# Main.net
KiCad netlist of a schematic drawn in Altium Designer
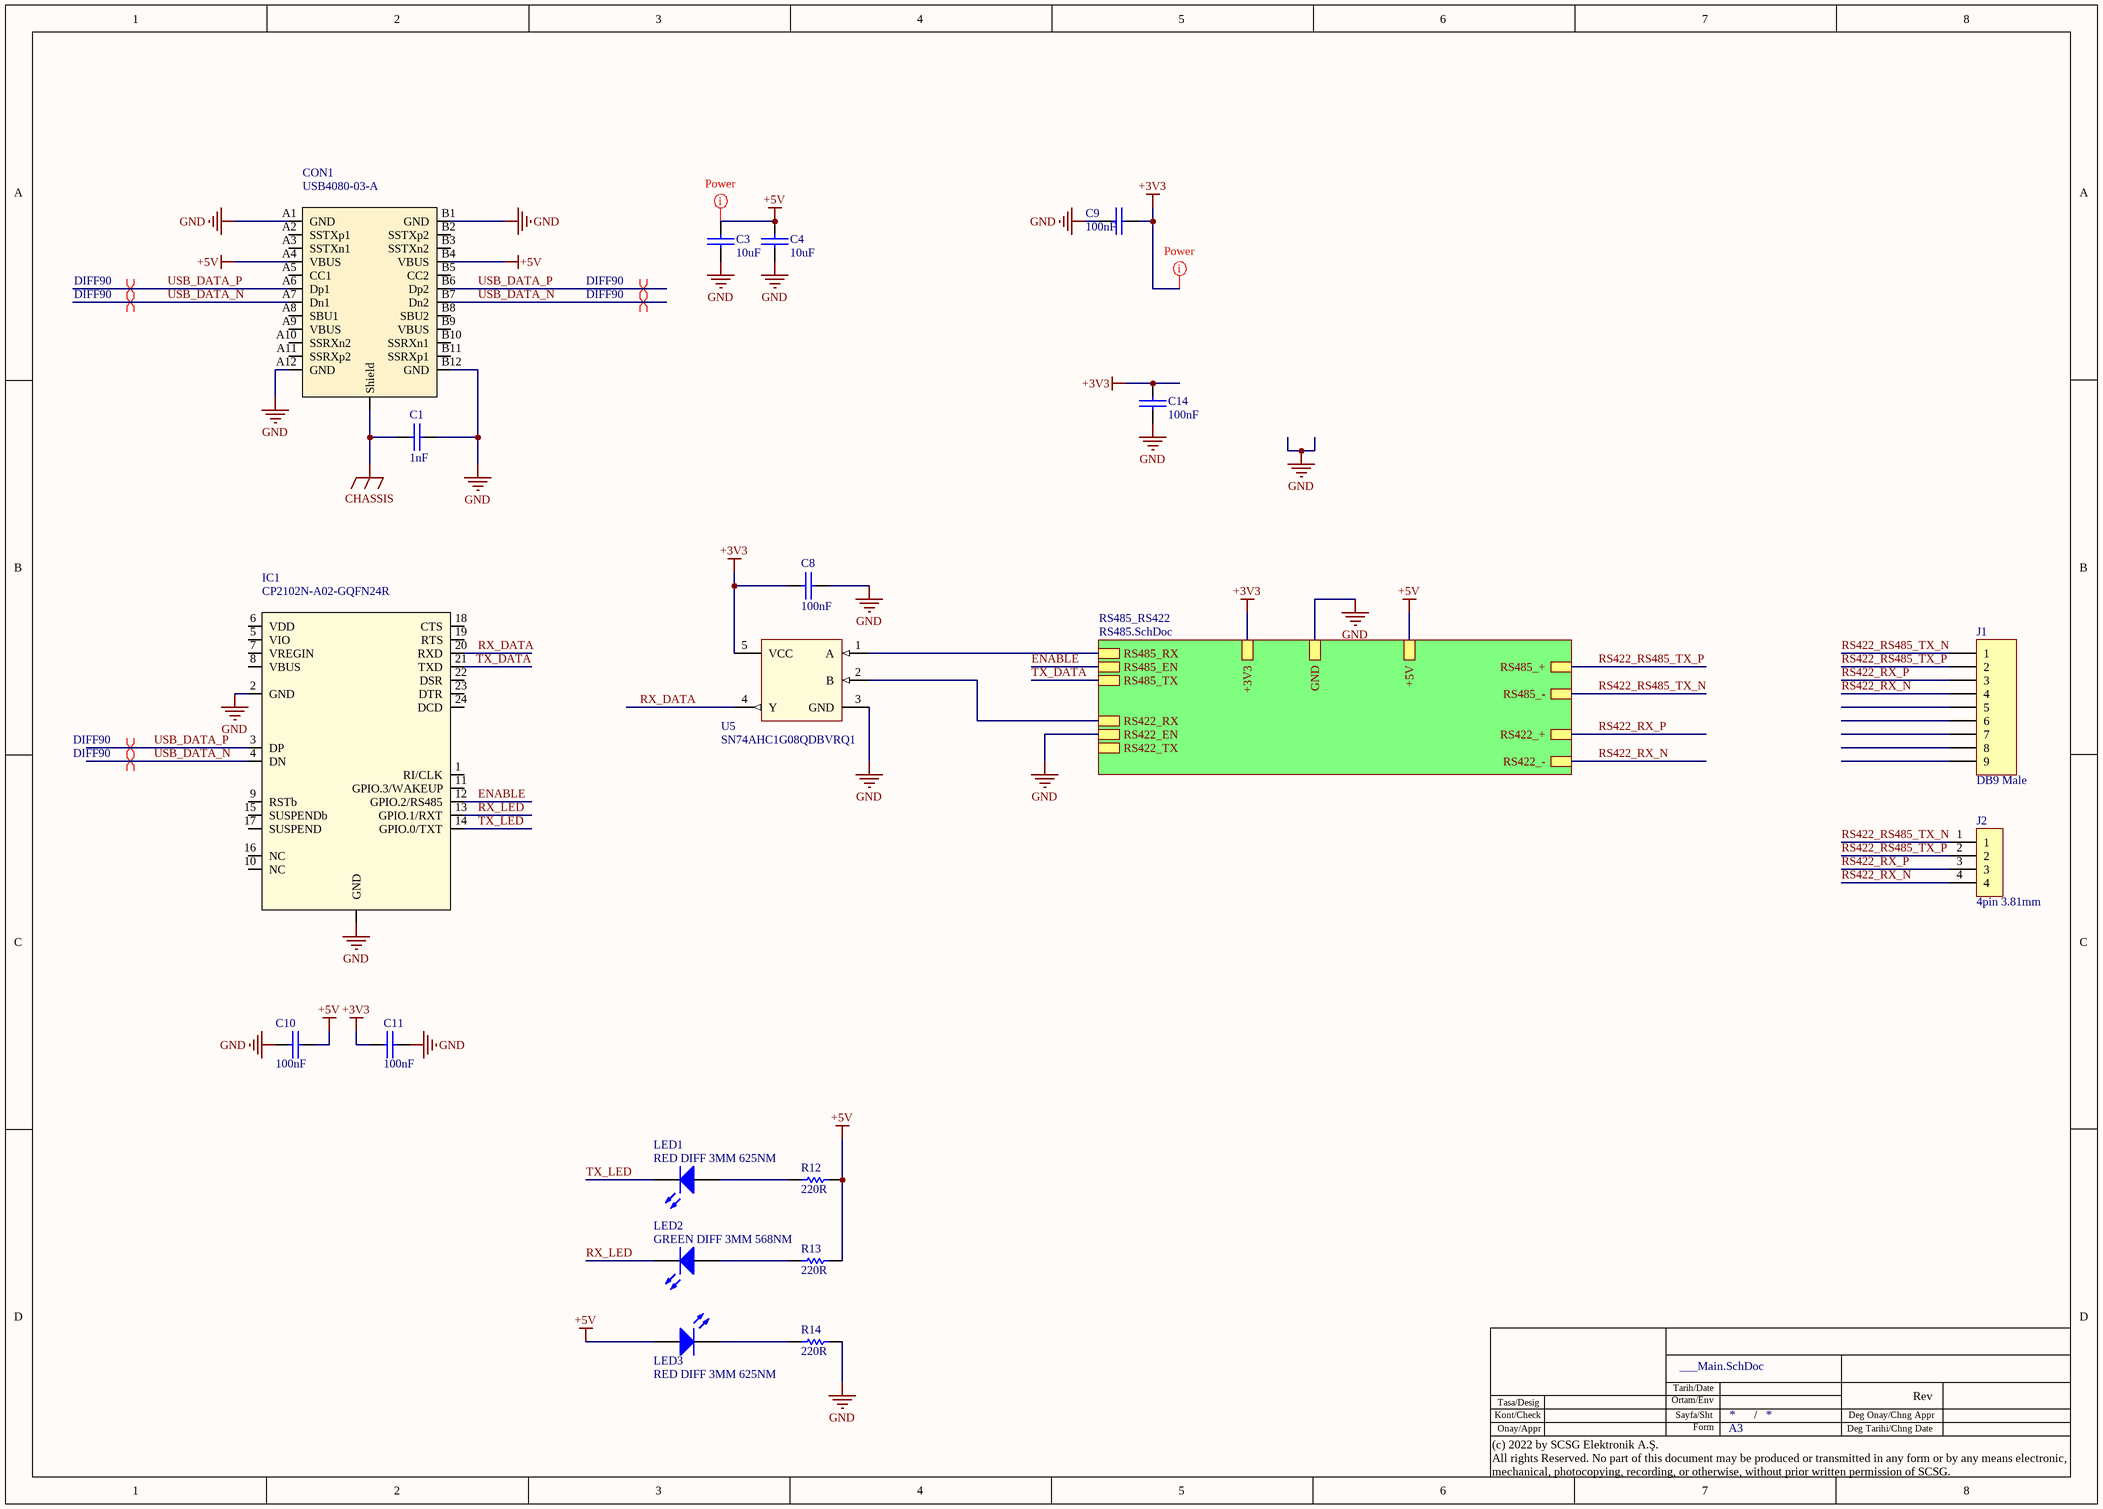
[diagram p0: ___Main.SchDoc]

(export (version "E")
  (design (tool "Eeschema 10.0.6"))
  (components
    (comp (ref "C1")
      (value "1nF")
      (footprint "C1206-N - H 1.75×L 3.4×W 1.8")
      (description "1nF, 1206, X7R, 2kV, % 10, AEC-Q200")
      (fields (field (name "MANUFACTURER") "Kemet") (field (name "TOLERANCE") "+10% -10%"))
      (libsource (lib "PavoLib") (part "CAPL10012820E"))
    )
    (comp (ref "C3")
      (value "10uF")
      (footprint "C0603-N")
      (description "10uF, 0603,  X5R, 10V, % 20")
      (fields (field (name "MANUFACTURER") "Samsung") (field (name "TOLERANCE") "20"))
      (libsource (lib "PAVO_REC_CAP") (part "CAP110050340F"))
    )
    (comp (ref "C4")
      (value "10uF")
      (footprint "C0603-N")
      (description "10uF, 0603,  X5R, 10V, % 20")
      (fields (field (name "MANUFACTURER") "Samsung") (field (name "TOLERANCE") "20"))
      (libsource (lib "PAVO_REC_CAP") (part "CAP110050340F"))
    )
    (comp (ref "C8")
      (value "100nF")
      (footprint "C0402-N")
      (description "100nF, 0402, X7R, 16V, % 10")
      (fields (field (name "TOLERANCE") "% 10") (field (name "MANUFACTURER") "Samsung"))
      (libsource (lib "PAVO_REC_CAP") (part "CAP110030425E"))
    )
    (comp (ref "C9")
      (value "100nF")
      (footprint "C0402-N")
      (description "100nF, 0402, X7R, 16V, % 10")
      (fields (field (name "TOLERANCE") "% 10") (field (name "MANUFACTURER") "Samsung"))
      (libsource (lib "PAVO_REC_CAP") (part "CAP110030425E"))
    )
    (comp (ref "C10")
      (value "100nF")
      (footprint "C0402-N")
      (description "100nF, 0402, X7R, 16V, % 10")
      (fields (field (name "TOLERANCE") "% 10") (field (name "MANUFACTURER") "Samsung"))
      (libsource (lib "PAVO_REC_CAP") (part "CAP110030425E"))
    )
    (comp (ref "C11")
      (value "100nF")
      (footprint "C0402-N")
      (description "100nF, 0402, X7R, 16V, % 10")
      (fields (field (name "TOLERANCE") "% 10") (field (name "MANUFACTURER") "Samsung"))
      (libsource (lib "PAVO_REC_CAP") (part "CAP110030425E"))
    )
    (comp (ref "C14")
      (value "100nF")
      (footprint "C0402-N")
      (description "100nF, 0402, X7R, 16V, % 10")
      (fields (field (name "TOLERANCE") "% 10") (field (name "MANUFACTURER") "Samsung"))
      (libsource (lib "PAVO_REC_CAP") (part "CAP110030425E"))
    )
    (comp (ref "CON1")
      (value "USB4080-03-A")
      (footprint "GCT_USB4080-03-A_REVA1")
      (description "USB Type C Rec, 3 Horizontal, SMT, Top mnt, 7.9mm body")
      (fields (field (name "MANUFACTURER") "Global Connector Technology"))
      (libsource (lib "Connectors") (part "USB4080-03-A"))
    )
    (comp (ref "IC1")
      (value "CP2102N-A02-GQFN24R")
      (footprint "QFN24")
      (description "IC Usb to Uart Bridge QFN24 / Usb Bridge, Usb to Uart Usb 2.0 Uart Interface 24-QFN (4X4)")
      (fields (field (name "MANUFACTURER") "Silicon Lab"))
      (libsource (lib "IntegratedCircuit") (part "CP2102N-A02-GQFN24R"))
    )
    (comp (ref "J1")
      (value "DB9 Male")
      (footprint "CON110090001")
      (description "DB9,Male,Edge Connect")
      (fields (field (name "Comment") "CON110090001"))
      (libsource (lib "TT") (part "CON110090001"))
    )
    (comp (ref "J2")
      (value "4pin 3.81mm")
      (footprint "PV04-3,81")
      (description "4 PIN 8A 160V 2.5 kVrms/60s")
      (fields (field (name "MANUFACTURER") "Euroclamp") (field (name "Comment") "CON1500412AE"))
      (libsource (lib "PavoLib") (part "CON1500412AE"))
    )
    (comp (ref "LED1")
      (value "RED DIFF 3MM 625NM")
      (footprint "RADIAL 3.2X5.4")
      (fields (field (name "MANUFACTURER") "Kingbright") (field (name "Comment") "LED0002WP710"))
      (libsource (lib "PavoLib") (part "LED0002WP710"))
    )
    (comp (ref "LED2")
      (value "GREEN DIFF 3MM 568NM")
      (footprint "RADIAL 3.2X5.4")
      (fields (field (name "MANUFACTURER") "Kingbright") (field (name "Comment") "LED0202WP710"))
      (libsource (lib "PavoLib") (part "LED0202WP710"))
    )
    (comp (ref "LED3")
      (value "RED DIFF 3MM 625NM")
      (footprint "RADIAL 3.2X5.4")
      (fields (field (name "MANUFACTURER") "Kingbright") (field (name "Comment") "LED0002WP710"))
      (libsource (lib "PavoLib") (part "LED0002WP710"))
    )
    (comp (ref "R12")
      (value "220R")
      (footprint "0402-N")
      (description "E24, 220R, 0402, %1")
      (fields (field (name "MANUFACTURER") "Panasonic - ECG") (field (name "TOLERANCE") "***"))
      (libsource (lib "RESE24") (part "RESE24002201"))
    )
    (comp (ref "R13")
      (value "220R")
      (footprint "0402-N")
      (description "E24, 220R, 0402, %1")
      (fields (field (name "MANUFACTURER") "Panasonic - ECG") (field (name "TOLERANCE") "***"))
      (libsource (lib "RESE24") (part "RESE24002201"))
    )
    (comp (ref "R14")
      (value "220R")
      (footprint "0402-N")
      (description "E24, 220R, 0402, %1")
      (fields (field (name "MANUFACTURER") "Panasonic - ECG") (field (name "TOLERANCE") "***"))
      (libsource (lib "RESE24") (part "RESE24002201"))
    )
    (comp (ref "U5")
      (value "SN74AHC1G08QDBVRQ1")
      (footprint "SOT23-5")
      (description "IC SNGL 2IN POS-AND GATE AUTOMOTIVE QUALIFIED")
      (fields (field (name "MANUFACTURER") "Texas Instruments") (field (name "Comment") "IC74AHC1G081"))
      (libsource (lib "PavoLib") (part "IC74AHC1G081"))
    )
  )
  (nets
    (net (code "1") (name "+3V3") (class "Default")
      (node (ref "C11") (pin "1") (pinfunction "1_1") (pintype "passive"))
      (node (ref "C14") (pin "2") (pinfunction "2_2") (pintype "passive"))
      (node (ref "C8") (pin "2") (pinfunction "2_2") (pintype "passive"))
      (node (ref "C9") (pin "1") (pinfunction "1_1") (pintype "passive"))
      (node (ref "U5") (pin "5") (pinfunction "VCC_5") (pintype "power_in"))
    )
    (net (code "2") (name "+5V") (class "Default")
      (node (ref "C10") (pin "1") (pinfunction "1_1") (pintype "passive"))
      (node (ref "C3") (pin "2") (pinfunction "2_2") (pintype "passive"))
      (node (ref "C4") (pin "2") (pinfunction "2_2") (pintype "passive"))
      (node (ref "CON1") (pin "A4") (pinfunction "VBUS_A4") (pintype "passive"))
      (node (ref "CON1") (pin "B4") (pinfunction "VBUS_B4") (pintype "passive"))
      (node (ref "LED3") (pin "1") (pinfunction "A_1") (pintype "passive"))
      (node (ref "R12") (pin "2") (pinfunction "2_2") (pintype "passive"))
      (node (ref "R13") (pin "2") (pinfunction "2_2") (pintype "passive"))
    )
    (net (code "3") (name "/ENABLE") (class "Default")
      (node (ref "IC1") (pin "12") (pinfunction "GPIO.2/RS485_12") (pintype "passive"))
    )
    (net (code "4") (name "/RS422_RS485_TX_N") (class "Default")
      (node (ref "J1") (pin "1") (pinfunction "1_1") (pintype "passive"))
      (node (ref "J2") (pin "1") (pinfunction "1_1") (pintype "passive"))
    )
    (net (code "5") (name "/RS422_RS485_TX_P") (class "Default")
      (node (ref "J1") (pin "2") (pinfunction "2_2") (pintype "passive"))
      (node (ref "J2") (pin "2") (pinfunction "2_2") (pintype "passive"))
    )
    (net (code "6") (name "/RS422_RX") (class "Default")
      (node (ref "U5") (pin "2") (pinfunction "B_2") (pintype "input"))
    )
    (net (code "7") (name "/RS422_RX_N") (class "Default")
      (node (ref "J1") (pin "4") (pinfunction "4_4") (pintype "passive"))
      (node (ref "J2") (pin "4") (pinfunction "4_4") (pintype "passive"))
    )
    (net (code "8") (name "/RS422_RX_P") (class "Default")
      (node (ref "J1") (pin "3") (pinfunction "3_3") (pintype "passive"))
      (node (ref "J2") (pin "3") (pinfunction "3_3") (pintype "passive"))
    )
    (net (code "10") (name "/RS485_RX") (class "Default")
      (node (ref "U5") (pin "1") (pinfunction "A_1") (pintype "input"))
    )
    (net (code "11") (name "/RX_DATA") (class "Default")
      (node (ref "IC1") (pin "20") (pinfunction "RXD_20") (pintype "passive"))
      (node (ref "U5") (pin "4") (pinfunction "Y_4") (pintype "output"))
    )
    (net (code "12") (name "/RX_LED") (class "Default")
      (node (ref "IC1") (pin "13") (pinfunction "GPIO.1/RXT_13") (pintype "passive"))
      (node (ref "LED2") (pin "2") (pinfunction "K_2") (pintype "passive"))
    )
    (net (code "13") (name "/TX_DATA") (class "Default")
      (node (ref "IC1") (pin "21") (pinfunction "TXD_21") (pintype "passive"))
    )
    (net (code "14") (name "/TX_LED") (class "Default")
      (node (ref "IC1") (pin "14") (pinfunction "GPIO.0/TXT_14") (pintype "passive"))
      (node (ref "LED1") (pin "2") (pinfunction "K_2") (pintype "passive"))
    )
    (net (code "15") (name "/USB_DATA_N") (class "Default")
      (node (ref "CON1") (pin "A7") (pinfunction "Dn1_A7") (pintype "passive"))
      (node (ref "CON1") (pin "B7") (pinfunction "Dn2_B7") (pintype "passive"))
      (node (ref "IC1") (pin "4") (pinfunction "DN_4") (pintype "passive"))
    )
    (net (code "16") (name "/USB_DATA_P") (class "Default")
      (node (ref "CON1") (pin "A6") (pinfunction "Dp1_A6") (pintype "passive"))
      (node (ref "CON1") (pin "B6") (pinfunction "Dp2_B6") (pintype "passive"))
      (node (ref "IC1") (pin "3") (pinfunction "DP_3") (pintype "passive"))
    )
    (net (code "17") (name "CHASSIS") (class "Default")
      (node (ref "C1") (pin "2") (pinfunction "2_2") (pintype "passive"))
      (node (ref "CON1") (pin "G") (pinfunction "Shield_G") (pintype "passive"))
    )
    (net (code "18") (name "GND") (class "Default")
      (node (ref "C1") (pin "1") (pinfunction "1_1") (pintype "passive"))
      (node (ref "C10") (pin "2") (pinfunction "2_2") (pintype "passive"))
      (node (ref "C11") (pin "2") (pinfunction "2_2") (pintype "passive"))
      (node (ref "C14") (pin "1") (pinfunction "1_1") (pintype "passive"))
      (node (ref "C3") (pin "1") (pinfunction "1_1") (pintype "passive"))
      (node (ref "C4") (pin "1") (pinfunction "1_1") (pintype "passive"))
      (node (ref "C8") (pin "1") (pinfunction "1_1") (pintype "passive"))
      (node (ref "C9") (pin "2") (pinfunction "2_2") (pintype "passive"))
      (node (ref "CON1") (pin "A1") (pinfunction "GND_A1") (pintype "passive"))
      (node (ref "CON1") (pin "A12") (pinfunction "GND_A12") (pintype "passive"))
      (node (ref "CON1") (pin "B1") (pinfunction "GND_B1") (pintype "passive"))
      (node (ref "CON1") (pin "B12") (pinfunction "GND_B12") (pintype "passive"))
      (node (ref "IC1") (pin "2") (pinfunction "GND_2") (pintype "passive"))
      (node (ref "IC1") (pin "25") (pinfunction "GND_25") (pintype "passive"))
      (node (ref "R14") (pin "2") (pinfunction "2_2") (pintype "passive"))
      (node (ref "U5") (pin "3") (pinfunction "GND_3") (pintype "power_in"))
    )
    (net (code "19") (name "Net-(LED1-A)") (class "Default")
      (node (ref "LED1") (pin "1") (pinfunction "A_1") (pintype "passive"))
      (node (ref "R12") (pin "1") (pinfunction "1_1") (pintype "passive"))
    )
    (net (code "20") (name "Net-(LED2-A)") (class "Default")
      (node (ref "LED2") (pin "1") (pinfunction "A_1") (pintype "passive"))
      (node (ref "R13") (pin "1") (pinfunction "1_1") (pintype "passive"))
    )
    (net (code "21") (name "Net-(LED3-K)") (class "Default")
      (node (ref "LED3") (pin "2") (pinfunction "K_2") (pintype "passive"))
      (node (ref "R14") (pin "1") (pinfunction "1_1") (pintype "passive"))
    )
    (net (code "22") (name "unconnected-(CON1-CC1-PadA5)") (class "Default")
      (node (ref "CON1") (pin "A5") (pinfunction "CC1_A5") (pintype "passive"))
    )
    (net (code "23") (name "unconnected-(CON1-CC2-PadB5)") (class "Default")
      (node (ref "CON1") (pin "B5") (pinfunction "CC2_B5") (pintype "passive"))
    )
    (net (code "24") (name "unconnected-(CON1-SBU1-PadA8)") (class "Default")
      (node (ref "CON1") (pin "A8") (pinfunction "SBU1_A8") (pintype "passive"))
    )
    (net (code "25") (name "unconnected-(CON1-SBU2-PadB8)") (class "Default")
      (node (ref "CON1") (pin "B8") (pinfunction "SBU2_B8") (pintype "passive"))
    )
    (net (code "26") (name "unconnected-(CON1-SSRXn1-PadB10)") (class "Default")
      (node (ref "CON1") (pin "B10") (pinfunction "SSRXn1_B10") (pintype "passive"))
    )
    (net (code "27") (name "unconnected-(CON1-SSRXn2-PadA10)") (class "Default")
      (node (ref "CON1") (pin "A10") (pinfunction "SSRXn2_A10") (pintype "passive"))
    )
    (net (code "28") (name "unconnected-(CON1-SSRXp1-PadB11)") (class "Default")
      (node (ref "CON1") (pin "B11") (pinfunction "SSRXp1_B11") (pintype "passive"))
    )
    (net (code "29") (name "unconnected-(CON1-SSRXp2-PadA11)") (class "Default")
      (node (ref "CON1") (pin "A11") (pinfunction "SSRXp2_A11") (pintype "passive"))
    )
    (net (code "30") (name "unconnected-(CON1-SSTXn1-PadA3)") (class "Default")
      (node (ref "CON1") (pin "A3") (pinfunction "SSTXn1_A3") (pintype "passive"))
    )
    (net (code "31") (name "unconnected-(CON1-SSTXn2-PadB3)") (class "Default")
      (node (ref "CON1") (pin "B3") (pinfunction "SSTXn2_B3") (pintype "passive"))
    )
    (net (code "32") (name "unconnected-(CON1-SSTXp1-PadA2)") (class "Default")
      (node (ref "CON1") (pin "A2") (pinfunction "SSTXp1_A2") (pintype "passive"))
    )
    (net (code "33") (name "unconnected-(CON1-SSTXp2-PadB2)") (class "Default")
      (node (ref "CON1") (pin "B2") (pinfunction "SSTXp2_B2") (pintype "passive"))
    )
    (net (code "34") (name "unconnected-(CON1-VBUS-PadA9)") (class "Default")
      (node (ref "CON1") (pin "A9") (pinfunction "VBUS_A9") (pintype "passive"))
    )
    (net (code "35") (name "unconnected-(CON1-VBUS-PadB9)") (class "Default")
      (node (ref "CON1") (pin "B9") (pinfunction "VBUS_B9") (pintype "passive"))
    )
    (net (code "36") (name "unconnected-(IC1-CTS-Pad18)") (class "Default")
      (node (ref "IC1") (pin "18") (pinfunction "CTS_18") (pintype "passive"))
    )
    (net (code "37") (name "unconnected-(IC1-DCD-Pad24)") (class "Default")
      (node (ref "IC1") (pin "24") (pinfunction "DCD_24") (pintype "passive"))
    )
    (net (code "38") (name "unconnected-(IC1-DSR-Pad22)") (class "Default")
      (node (ref "IC1") (pin "22") (pinfunction "DSR_22") (pintype "passive"))
    )
    (net (code "39") (name "unconnected-(IC1-DTR-Pad23)") (class "Default")
      (node (ref "IC1") (pin "23") (pinfunction "DTR_23") (pintype "passive"))
    )
    (net (code "40") (name "unconnected-(IC1-GPIO.3{slash}WAKEUP-Pad11)") (class "Default")
      (node (ref "IC1") (pin "11") (pinfunction "GPIO.3/WAKEUP_11") (pintype "passive"))
    )
    (net (code "41") (name "unconnected-(IC1-NC-Pad10)") (class "Default")
      (node (ref "IC1") (pin "10") (pinfunction "NC_10") (pintype "passive"))
    )
    (net (code "42") (name "unconnected-(IC1-NC-Pad16)") (class "Default")
      (node (ref "IC1") (pin "16") (pinfunction "NC_16") (pintype "passive"))
    )
    (net (code "43") (name "unconnected-(IC1-RI{slash}CLK-Pad1)") (class "Default")
      (node (ref "IC1") (pin "1") (pinfunction "RI/CLK_1") (pintype "passive"))
    )
    (net (code "44") (name "unconnected-(IC1-RSTb-Pad9)") (class "Default")
      (node (ref "IC1") (pin "9") (pinfunction "RSTb_9") (pintype "passive"))
    )
    (net (code "45") (name "unconnected-(IC1-RTS-Pad19)") (class "Default")
      (node (ref "IC1") (pin "19") (pinfunction "RTS_19") (pintype "passive"))
    )
    (net (code "46") (name "unconnected-(IC1-SUSPEND-Pad17)") (class "Default")
      (node (ref "IC1") (pin "17") (pinfunction "SUSPEND_17") (pintype "passive"))
    )
    (net (code "47") (name "unconnected-(IC1-SUSPENDb-Pad15)") (class "Default")
      (node (ref "IC1") (pin "15") (pinfunction "SUSPENDb_15") (pintype "passive"))
    )
    (net (code "48") (name "unconnected-(IC1-VBUS-Pad8)") (class "Default")
      (node (ref "IC1") (pin "8") (pinfunction "VBUS_8") (pintype "passive"))
    )
    (net (code "49") (name "unconnected-(IC1-VDD-Pad6)") (class "Default")
      (node (ref "IC1") (pin "6") (pinfunction "VDD_6") (pintype "passive"))
    )
    (net (code "50") (name "unconnected-(IC1-VIO-Pad5)") (class "Default")
      (node (ref "IC1") (pin "5") (pinfunction "VIO_5") (pintype "passive"))
    )
    (net (code "51") (name "unconnected-(IC1-VREGIN-Pad7)") (class "Default")
      (node (ref "IC1") (pin "7") (pinfunction "VREGIN_7") (pintype "passive"))
    )
    (net (code "52") (name "unconnected-(J1-Pad5)") (class "Default")
      (node (ref "J1") (pin "5") (pinfunction "5_5") (pintype "passive"))
    )
    (net (code "53") (name "unconnected-(J1-Pad6)") (class "Default")
      (node (ref "J1") (pin "6") (pinfunction "6_6") (pintype "passive"))
    )
    (net (code "54") (name "unconnected-(J1-Pad7)") (class "Default")
      (node (ref "J1") (pin "7") (pinfunction "7_7") (pintype "passive"))
    )
    (net (code "55") (name "unconnected-(J1-Pad8)") (class "Default")
      (node (ref "J1") (pin "8") (pinfunction "8_8") (pintype "passive"))
    )
    (net (code "56") (name "unconnected-(J1-Pad9)") (class "Default")
      (node (ref "J1") (pin "9") (pinfunction "9_9") (pintype "passive"))
    )
  )
)
